# 07_-PowerSupply.net
KiCad netlist of a schematic drawn in Altium Designer
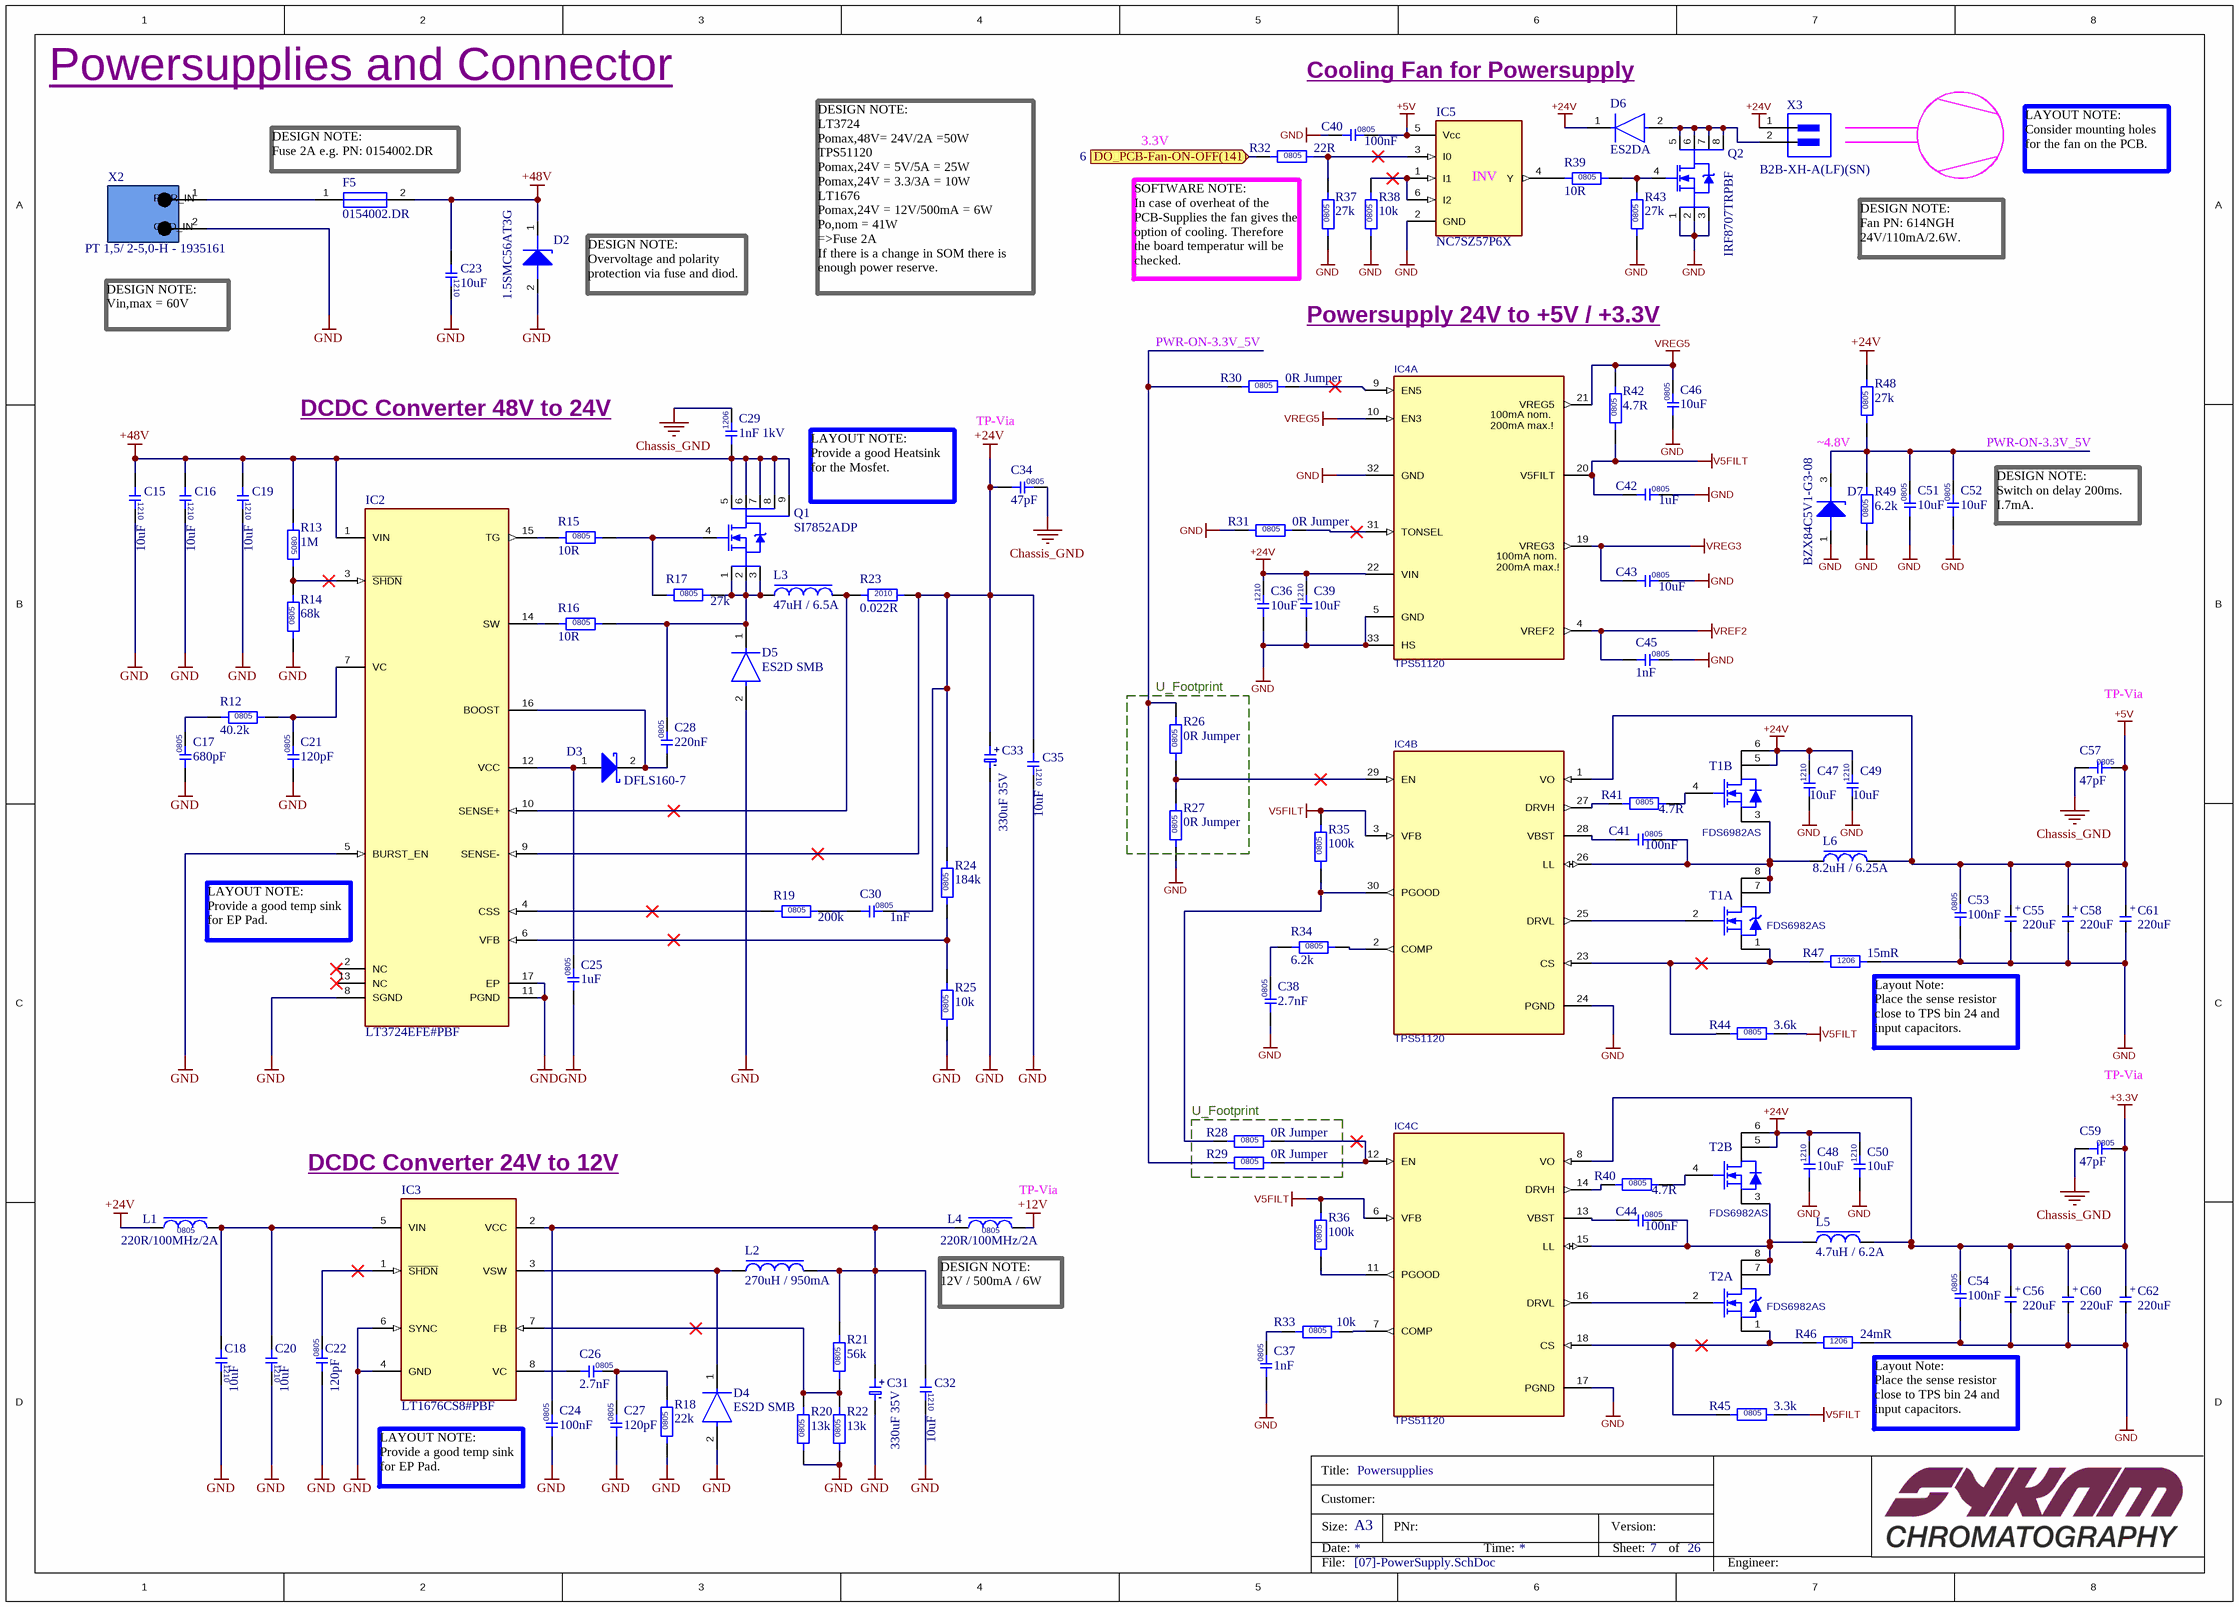
[diagram p0: [07]-PowerSupply.SchDoc]

(export (version "E")
  (design (tool "Eeschema 10.0.6"))
  (components
    (comp (ref "C15")
      (value "10uF")
      (footprint "C1210")
      (description "CAP CER 10UF 50V X7R 1210")
      (fields
        (field (name "MANUFACTURER") "KEMET")
        (field (name "MANUFACTURER PART NUMBER") "C1210C106K5RACTU")
      )
      (libsource (lib "ToradexMainBoard-V0I1") (part "C_10uF_C1210C106K5RACTU"))
    )
    (comp (ref "C16")
      (value "10uF")
      (footprint "C1210")
      (description "CAP CER 10UF 50V X7R 1210")
      (fields
        (field (name "MANUFACTURER") "KEMET")
        (field (name "MANUFACTURER PART NUMBER") "C1210C106K5RACTU")
      )
      (libsource (lib "ToradexMainBoard-V0I1") (part "C_10uF_C1210C106K5RACTU"))
    )
    (comp (ref "C17")
      (value "680pF")
      (footprint "C0805")
      (description "Cap Ceramic 680pF 50V X7R 10% SMD 0805 125C T/R")
      (fields
        (field (name "MANUFACTURER") "KEMET")
        (field (name "MANUFACTURER PART NUMBER") "C0805C681K5RACTU")
      )
      (libsource (lib "ToradexMainBoard-V0I1") (part "C_680pF_C0805C681K5RACTU"))
    )
    (comp (ref "C18")
      (value "10uF")
      (footprint "C1210")
      (description "CAP CER 10UF 50V X7R 1210")
      (fields
        (field (name "MANUFACTURER") "KEMET")
        (field (name "MANUFACTURER PART NUMBER") "C1210C106K5RACTU")
      )
      (libsource (lib "ToradexMainBoard-V0I1") (part "C_10uF_C1210C106K5RACTU"))
    )
    (comp (ref "C19")
      (value "10uF")
      (footprint "C1210")
      (description "CAP CER 10UF 50V X7R 1210")
      (fields
        (field (name "MANUFACTURER") "KEMET")
        (field (name "MANUFACTURER PART NUMBER") "C1210C106K5RACTU")
      )
      (libsource (lib "ToradexMainBoard-V0I1") (part "C_10uF_C1210C106K5RACTU"))
    )
    (comp (ref "C20")
      (value "10uF")
      (footprint "C1210")
      (description "CAP CER 10UF 50V X7R 1210")
      (fields
        (field (name "MANUFACTURER") "KEMET")
        (field (name "MANUFACTURER PART NUMBER") "C1210C106K5RACTU")
      )
      (libsource (lib "ToradexMainBoard-V0I1") (part "C_10uF_C1210C106K5RACTU"))
    )
    (comp (ref "C21")
      (value "120pF")
      (footprint "C0805")
      (description "Cap Ceramic 120pF 50V X7R 10% SMD 0805 125C T/R")
      (fields
        (field (name "MANUFACTURER") "Kyocera AVX")
        (field (name "MANUFACTURER PART NUMBER") "08055C121KAT2A")
      )
      (libsource (lib "ToradexMainBoard-V0I1") (part "C_120pF_08055C121KAT2A"))
    )
    (comp (ref "C22")
      (value "120pF")
      (footprint "C0805")
      (description "Cap Ceramic 120pF 50V X7R 10% SMD 0805 125C T/R")
      (fields
        (field (name "MANUFACTURER") "Kyocera AVX")
        (field (name "MANUFACTURER PART NUMBER") "08055C121KAT2A")
      )
      (libsource (lib "ToradexMainBoard-V0I1") (part "C_120pF_08055C121KAT2A"))
    )
    (comp (ref "C23")
      (value "10uF")
      (footprint "C1210")
      (description "CAP CER 10UF 50V X7R 1210")
      (fields
        (field (name "MANUFACTURER") "KEMET")
        (field (name "MANUFACTURER PART NUMBER") "C1210C106K5RACTU")
      )
      (libsource (lib "ToradexMainBoard-V0I1") (part "C_10uF_C1210C106K5RACTU"))
    )
    (comp (ref "C24")
      (value "100nF")
      (footprint "C0805")
      (description "CAP CER 0.1UF 50V X7R 0805")
      (fields
        (field (name "MANUFACTURER PART NUMBER") "CC0805KRX7R9BB104")
        (field (name "TOLERANCE") "10%")
        (field (name "PCBCHECKED") "initials after Checked")
        (field (name "SCHCHECKED") "Initials after checked")
      )
      (libsource (lib "ToradexMainBoard-V0I1") (part "C_100nF_CC0805KRX7R9BB104"))
    )
    (comp (ref "C25")
      (value "1uF")
      (footprint "C0805")
      (description "Cap Ceramic 1uF 50V X7R 10% SMD 0805 125C Blister T/R")
      (fields
        (field (name "MANUFACTURER PART NUMBER") "CC0805KKX7R9BB105")
        (field (name "TOLERANCE") "10%")
        (field (name "PCBCHECKED") "initials after Checked")
        (field (name "SCHCHECKED") "Initials after checked")
      )
      (libsource (lib "ToradexMainBoard-V0I1") (part "C_1uF_CC0805KKX7R9BB105"))
    )
    (comp (ref "C26")
      (value "2.7nF")
      (footprint "C0805")
      (fields
        (field (name "MANUFACTURER") "KEMET")
        (field (name "MANUFACTURER PART NUMBER") "C0805C272K5RACTU")
        (field (name "TOLERANCE") "10%")
      )
      (libsource (lib "ToradexMainBoard-V0I1") (part "C_2.7nF_C0805C272K5RACTU"))
    )
    (comp (ref "C27")
      (value "120pF")
      (footprint "C0805")
      (description "Cap Ceramic 120pF 50V X7R 10% SMD 0805 125C T/R")
      (fields
        (field (name "MANUFACTURER") "Kyocera AVX")
        (field (name "MANUFACTURER PART NUMBER") "08055C121KAT2A")
      )
      (libsource (lib "ToradexMainBoard-V0I1") (part "C_120pF_08055C121KAT2A"))
    )
    (comp (ref "C28")
      (value "220nF")
      (footprint "C0805")
      (description "CAP CER 0.22UF 50V X7R 0805")
      (fields
        (field (name "MANUFACTURER") "KEMET")
        (field (name "MANUFACTURER PART NUMBER") "C0805C224K5RACTU")
      )
      (libsource (lib "ToradexMainBoard-V0I1") (part "C_220nF_C0805C224K5RACTU"))
    )
    (comp (ref "C29")
      (value "1nF 1kV")
      (footprint "C1206")
      (description "CAP CER 1000PF 1KV X7S 1206")
      (fields
        (field (name "MANUFACTURER") "TDK")
        (field (name "MANUFACTURER PART NUMBER") "CGA5F1X7S3A102M085AE")
      )
      (libsource (lib "Sykam-LagerBauteile1-B") (part "C_1nF-1kV-CGA5F1X7S3A102M085AE"))
    )
    (comp (ref "C30")
      (value "1nF")
      (footprint "C0805")
      (description "Multilayer Ceramic Capacitors MLCC - SMD/SMT 50volts 1000pF X7R 10%")
      (fields
        (field (name "MANUFACTURER") "KEMET")
        (field (name "MANUFACTURER PART NUMBER") "C0805C102K5RAC7411")
      )
      (libsource (lib "ToradexMainBoard-V0I1") (part "C_1nF_C0805C102K5RAC7411"))
    )
    (comp (ref "C31")
      (value "330uF 35V")
      (footprint "C_EEEFP1V331AP")
      (description "GLOVE, POLYAMIDE, L/FREE, PU, SIZE 6 - More Details")
      (fields
        (field (name "MANUFACTURER") "Panasonic")
        (field (name "MANUFACTURER PART NUMBER") "EEEFP1V331AP")
      )
      (libsource (lib "ToradexMainBoard-V0I1") (part "C_330uF_35V_EEEFP1V331AP"))
    )
    (comp (ref "C32")
      (value "10uF")
      (footprint "C1210")
      (description "CAP CER 10UF 50V X7R 1210")
      (fields
        (field (name "MANUFACTURER") "KEMET")
        (field (name "MANUFACTURER PART NUMBER") "C1210C106K5RACTU")
      )
      (libsource (lib "ToradexMainBoard-V0I1") (part "C_10uF_C1210C106K5RACTU"))
    )
    (comp (ref "C33")
      (value "330uF 35V")
      (footprint "C_EEEFP1V331AP")
      (description "GLOVE, POLYAMIDE, L/FREE, PU, SIZE 6 - More Details")
      (fields
        (field (name "MANUFACTURER") "Panasonic")
        (field (name "MANUFACTURER PART NUMBER") "EEEFP1V331AP")
      )
      (libsource (lib "ToradexMainBoard-V0I1") (part "C_330uF_35V_EEEFP1V331AP"))
    )
    (comp (ref "C34")
      (value "47pF")
      (footprint "C0805")
      (description "Capacitor: ceramic; MLCC; 47pF; 100V; C0G; ±5%; SMD; 0805")
      (fields (field (name "MANUFACTURER PART NUMBER") "C0805C470J1GACTU") (field (name "TOLERANCE") "5%"))
      (libsource (lib "ToradexMainBoard-V0I1") (part "C_47pF_C0805C470J1GACTU"))
    )
    (comp (ref "C35")
      (value "10uF")
      (footprint "C1210")
      (description "CAP CER 10UF 50V X7R 1210")
      (fields
        (field (name "MANUFACTURER") "KEMET")
        (field (name "MANUFACTURER PART NUMBER") "C1210C106K5RACTU")
      )
      (libsource (lib "ToradexMainBoard-V0I1") (part "C_10uF_C1210C106K5RACTU"))
    )
    (comp (ref "C36")
      (value "10uF")
      (footprint "C1210")
      (description "CAP CER 10UF 50V X7R 1210")
      (fields
        (field (name "MANUFACTURER") "KEMET")
        (field (name "MANUFACTURER PART NUMBER") "C1210C106K5RACTU")
      )
      (libsource (lib "Sykam-LagerBauteile1") (part "C_10uF_C1210C106K5RACTU"))
    )
    (comp (ref "C37")
      (value "1nF")
      (footprint "C0805")
      (description "Multilayer Ceramic Capacitors MLCC - SMD/SMT 50volts 1000pF X7R 10%")
      (fields
        (field (name "MANUFACTURER") "KEMET")
        (field (name "MANUFACTURER PART NUMBER") "C0805C102K5RAC7411")
      )
      (libsource (lib "Sykam-LagerBauteile1") (part "C_1nF_C0805C102K5RAC7411"))
    )
    (comp (ref "C38")
      (value "2.7nF")
      (footprint "C0805")
      (fields
        (field (name "MANUFACTURER") "KEMET")
        (field (name "MANUFACTURER PART NUMBER") "C0805C272K5RACTU")
        (field (name "TOLERANCE") "10%")
      )
      (libsource (lib "Sykam-LagerBauteile1") (part "C_2.7nF_C0805C272K5RACTU"))
    )
    (comp (ref "C39")
      (value "10uF")
      (footprint "C1210")
      (description "CAP CER 10UF 50V X7R 1210")
      (fields
        (field (name "MANUFACTURER") "KEMET")
        (field (name "MANUFACTURER PART NUMBER") "C1210C106K5RACTU")
      )
      (libsource (lib "Sykam-LagerBauteile1") (part "C_10uF_C1210C106K5RACTU"))
    )
    (comp (ref "C40")
      (value "100nF")
      (footprint "C0805")
      (description "CAP CER 0.1UF 50V X7R 0805")
      (fields
        (field (name "MANUFACTURER PART NUMBER") "CC0805KRX7R9BB104")
        (field (name "TOLERANCE") "10%")
        (field (name "PCBCHECKED") "initials after Checked")
        (field (name "SCHCHECKED") "Initials after checked")
      )
      (libsource (lib "Sykam-LagerBauteile1") (part "C_100nF_CC0805KRX7R9BB104"))
    )
    (comp (ref "C41")
      (value "100nF")
      (footprint "C0805")
      (description "CAP CER 0.1UF 50V X7R 0805")
      (fields
        (field (name "MANUFACTURER PART NUMBER") "CC0805KRX7R9BB104")
        (field (name "TOLERANCE") "10%")
        (field (name "PCBCHECKED") "initials after Checked")
        (field (name "SCHCHECKED") "Initials after checked")
      )
      (libsource (lib "Sykam-LagerBauteile1") (part "C_100nF_CC0805KRX7R9BB104"))
    )
    (comp (ref "C42")
      (value "1uF")
      (footprint "C0805")
      (description "Cap Ceramic 1uF 50V X7R 10% SMD 0805 125C Blister T/R")
      (fields
        (field (name "MANUFACTURER PART NUMBER") "CC0805KKX7R9BB105")
        (field (name "TOLERANCE") "10%")
        (field (name "PCBCHECKED") "initials after Checked")
        (field (name "SCHCHECKED") "Initials after checked")
      )
      (libsource (lib "Sykam-LagerBauteile1") (part "C_1uF_CC0805KKX7R9BB105"))
    )
    (comp (ref "C43")
      (value "10uF")
      (footprint "C0805")
      (description "0805 10 uF 50 V ±20% Tolerance X5R Multilayer Ceramic Capacitor")
      (fields
        (field (name "MANUFACTURER") "Murata")
        (field (name "MANUFACTURER PART NUMBER") "GRM21BR6YA106ME43L")
      )
      (libsource (lib "Sykam-LagerBauteile1") (part "C_10uF_GRM21BR6YA106ME43L"))
    )
    (comp (ref "C44")
      (value "100nF")
      (footprint "C0805")
      (description "CAP CER 0.1UF 50V X7R 0805")
      (fields
        (field (name "MANUFACTURER PART NUMBER") "CC0805KRX7R9BB104")
        (field (name "TOLERANCE") "10%")
        (field (name "PCBCHECKED") "initials after Checked")
        (field (name "SCHCHECKED") "Initials after checked")
      )
      (libsource (lib "Sykam-LagerBauteile1") (part "C_100nF_CC0805KRX7R9BB104"))
    )
    (comp (ref "C45")
      (value "1nF")
      (footprint "C0805")
      (description "Multilayer Ceramic Capacitors MLCC - SMD/SMT 50volts 1000pF X7R 10%")
      (fields
        (field (name "MANUFACTURER") "KEMET")
        (field (name "MANUFACTURER PART NUMBER") "C0805C102K5RAC7411")
      )
      (libsource (lib "Sykam-LagerBauteile1") (part "C_1nF_C0805C102K5RAC7411"))
    )
    (comp (ref "C46")
      (value "10uF")
      (footprint "C0805")
      (description "0805 10 uF 50 V ±20% Tolerance X5R Multilayer Ceramic Capacitor")
      (fields
        (field (name "MANUFACTURER") "Murata")
        (field (name "MANUFACTURER PART NUMBER") "GRM21BR6YA106ME43L")
      )
      (libsource (lib "Sykam-LagerBauteile1") (part "C_10uF_GRM21BR6YA106ME43L"))
    )
    (comp (ref "C47")
      (value "10uF")
      (footprint "C1210")
      (description "CAP CER 10UF 50V X7R 1210")
      (fields
        (field (name "MANUFACTURER") "KEMET")
        (field (name "MANUFACTURER PART NUMBER") "C1210C106K5RACTU")
      )
      (libsource (lib "Sykam-LagerBauteile1") (part "C_10uF_C1210C106K5RACTU"))
    )
    (comp (ref "C48")
      (value "10uF")
      (footprint "C1210")
      (description "CAP CER 10UF 50V X7R 1210")
      (fields
        (field (name "MANUFACTURER") "KEMET")
        (field (name "MANUFACTURER PART NUMBER") "C1210C106K5RACTU")
      )
      (libsource (lib "Sykam-LagerBauteile1") (part "C_10uF_C1210C106K5RACTU"))
    )
    (comp (ref "C49")
      (value "10uF")
      (footprint "C1210")
      (description "CAP CER 10UF 50V X7R 1210")
      (fields
        (field (name "MANUFACTURER") "KEMET")
        (field (name "MANUFACTURER PART NUMBER") "C1210C106K5RACTU")
      )
      (libsource (lib "Sykam-LagerBauteile1") (part "C_10uF_C1210C106K5RACTU"))
    )
    (comp (ref "C50")
      (value "10uF")
      (footprint "C1210")
      (description "CAP CER 10UF 50V X7R 1210")
      (fields
        (field (name "MANUFACTURER") "KEMET")
        (field (name "MANUFACTURER PART NUMBER") "C1210C106K5RACTU")
      )
      (libsource (lib "Sykam-LagerBauteile1") (part "C_10uF_C1210C106K5RACTU"))
    )
    (comp (ref "C51")
      (value "10uF")
      (footprint "C0805")
      (description "0805 10 uF 50 V ±20% Tolerance X5R Multilayer Ceramic Capacitor")
      (fields
        (field (name "MANUFACTURER") "Murata")
        (field (name "MANUFACTURER PART NUMBER") "GRM21BR6YA106ME43L")
      )
      (libsource (lib "ToradexMainBoard-V0I1") (part "C_10uF_GRM21BR6YA106ME43L"))
    )
    (comp (ref "C52")
      (value "10uF")
      (footprint "C0805")
      (description "0805 10 uF 50 V ±20% Tolerance X5R Multilayer Ceramic Capacitor")
      (fields
        (field (name "MANUFACTURER") "Murata")
        (field (name "MANUFACTURER PART NUMBER") "GRM21BR6YA106ME43L")
      )
      (libsource (lib "ToradexMainBoard-V0I1") (part "C_10uF_GRM21BR6YA106ME43L"))
    )
    (comp (ref "C53")
      (value "100nF")
      (footprint "C0805")
      (description "CAP CER 0.1UF 50V X7R 0805")
      (fields
        (field (name "MANUFACTURER PART NUMBER") "CC0805KRX7R9BB104")
        (field (name "TOLERANCE") "10%")
        (field (name "PCBCHECKED") "initials after Checked")
        (field (name "SCHCHECKED") "Initials after checked")
      )
      (libsource (lib "Sykam-LagerBauteile1") (part "C_100nF_CC0805KRX7R9BB104"))
    )
    (comp (ref "C54")
      (value "100nF")
      (footprint "C0805")
      (description "CAP CER 0.1UF 50V X7R 0805")
      (fields
        (field (name "MANUFACTURER PART NUMBER") "CC0805KRX7R9BB104")
        (field (name "TOLERANCE") "10%")
        (field (name "PCBCHECKED") "initials after Checked")
        (field (name "SCHCHECKED") "Initials after checked")
      )
      (libsource (lib "Sykam-LagerBauteile1") (part "C_100nF_CC0805KRX7R9BB104"))
    )
    (comp (ref "C55")
      (value "220uF")
      (footprint "C_220uF_TAN_TPSD227M010R0100")
      (description "CAPACITOR, TANTALUM")
      (fields
        (field (name "MANUFACTURER") "Kyocera AVX")
        (field (name "MANUFACTURER PART NUMBER") "TPSD227M010R0100")
      )
      (libsource (lib "Sykam-LagerBauteile1") (part "C_220uF_TAN_TPSD227M010R0100"))
    )
    (comp (ref "C56")
      (value "220uF")
      (footprint "C_220uF_TAN_TPSD227M010R0100")
      (description "CAPACITOR, TANTALUM")
      (fields
        (field (name "MANUFACTURER") "Kyocera AVX")
        (field (name "MANUFACTURER PART NUMBER") "TPSD227M010R0100")
      )
      (libsource (lib "Sykam-LagerBauteile1") (part "C_220uF_TAN_TPSD227M010R0100"))
    )
    (comp (ref "C57")
      (value "47pF")
      (footprint "C0805")
      (description "Capacitor: ceramic; MLCC; 47pF; 100V; C0G; ±5%; SMD; 0805")
      (fields (field (name "MANUFACTURER PART NUMBER") "C0805C470J1GACTU") (field (name "TOLERANCE") "5%"))
      (libsource (lib "ToradexMainBoard-V0I1") (part "C_47pF_C0805C470J1GACTU"))
    )
    (comp (ref "C58")
      (value "220uF")
      (footprint "C_220uF_TAN_TPSD227M010R0100")
      (description "CAPACITOR, TANTALUM")
      (fields
        (field (name "MANUFACTURER") "Kyocera AVX")
        (field (name "MANUFACTURER PART NUMBER") "TPSD227M010R0100")
      )
      (libsource (lib "Sykam-LagerBauteile1") (part "C_220uF_TAN_TPSD227M010R0100"))
    )
    (comp (ref "C59")
      (value "47pF")
      (footprint "C0805")
      (description "Capacitor: ceramic; MLCC; 47pF; 100V; C0G; ±5%; SMD; 0805")
      (fields (field (name "MANUFACTURER PART NUMBER") "C0805C470J1GACTU") (field (name "TOLERANCE") "5%"))
      (libsource (lib "ToradexMainBoard-V0I1") (part "C_47pF_C0805C470J1GACTU"))
    )
    (comp (ref "C60")
      (value "220uF")
      (footprint "C_220uF_TAN_TPSD227M010R0100")
      (description "CAPACITOR, TANTALUM")
      (fields
        (field (name "MANUFACTURER") "Kyocera AVX")
        (field (name "MANUFACTURER PART NUMBER") "TPSD227M010R0100")
      )
      (libsource (lib "Sykam-LagerBauteile1") (part "C_220uF_TAN_TPSD227M010R0100"))
    )
    (comp (ref "C61")
      (value "220uF")
      (footprint "C_220uF_TAN_TPSD227M010R0100")
      (description "CAPACITOR, TANTALUM")
      (fields
        (field (name "MANUFACTURER") "Kyocera AVX")
        (field (name "MANUFACTURER PART NUMBER") "TPSD227M010R0100")
      )
      (libsource (lib "Sykam-LagerBauteile1") (part "C_220uF_TAN_TPSD227M010R0100"))
    )
    (comp (ref "C62")
      (value "220uF")
      (footprint "C_220uF_TAN_TPSD227M010R0100")
      (description "CAPACITOR, TANTALUM")
      (fields
        (field (name "MANUFACTURER") "Kyocera AVX")
        (field (name "MANUFACTURER PART NUMBER") "TPSD227M010R0100")
      )
      (libsource (lib "Sykam-LagerBauteile1") (part "C_220uF_TAN_TPSD227M010R0100"))
    )
    (comp (ref "D2")
      (value "1.5SMC56AT3G")
      (footprint "D-TVS_SMC_UNI")
      (description "TVS DIODE 47.8V 77V SMC")
      (fields (field (name "MANUFACTURER") "ON Semiconductor"))
      (libsource (lib "ToradexMainBoard-V0I1") (part "D_TVS_1.5SMC56AT3G"))
    )
    (comp (ref "D3")
      (value "DFLS160-7")
      (footprint "D_POWERDI123")
      (description "DIODES INC. - DFLS160-7 - Schottky Rectifier, 60 V, 1 A, Single, PowerDI 123, 2 Pins, 500 mV")
      (fields (field (name "MANUFACTURER") "Diodes"))
      (libsource (lib "ToradexMainBoard-V0I1") (part "D_DFLS160-7"))
    )
    (comp (ref "D4")
      (value "ES2D SMB")
      (footprint "FB-SMB")
      (description "ON SEMICONDUCTOR - ES2D - Fast / Ultrafast Diode, 200 V, 2 A, Single, 900 mV, 20 ns, 50 A")
      (fields
        (field (name "MANUFACTURER") "ON Semiconductor / Fairchild")
        (field (name "MANUFACTURER PART NUMBER") "ES2D")
      )
      (libsource (lib "ToradexMainBoard-V0I1") (part "D_ES2D-SMB"))
    )
    (comp (ref "D5")
      (value "ES2D SMB")
      (footprint "FB-SMB")
      (description "ON SEMICONDUCTOR - ES2D - Fast / Ultrafast Diode, 200 V, 2 A, Single, 900 mV, 20 ns, 50 A")
      (fields
        (field (name "MANUFACTURER") "ON Semiconductor / Fairchild")
        (field (name "MANUFACTURER PART NUMBER") "ES2D")
      )
      (libsource (lib "ToradexMainBoard-V0I1") (part "D_ES2D-SMB"))
    )
    (comp (ref "D6")
      (value "ES2DA")
      (footprint "FP-SMA-MFG")
      (description "DIODE GEN PURP 200V 2A SMA")
      (fields (field (name "MANUFACTURER") "Diodes") (field (name "MANUFACTURER PART NUMBER") "ES2DA-13-F"))
      (libsource (lib "Sykam-LagerBauteile1-B") (part "D_ES2DA-13-F"))
    )
    (comp (ref "D7")
      (value "BZX84C5V1-G3-08")
      (footprint "BZX84C5.1V-SOT-23-3")
      (description "Zener Diodes 5.1 Volt 0.35W 5%")
      (fields (field (name "MANUFACTURER") "Vishay") (field (name "TOLERANCE") "5%"))
      (libsource (lib "ToradexMainBoard-V0I1") (part "D_BZX84C5V1-G3-08"))
    )
    (comp (ref "F5")
      (value "0154002.DR")
      (footprint "F_FUSE-154002")
      (description "LITTELFUSE   0154002.DR.   FUSE BLOCK W/ 2A FUSE, FAST ACTING")
      (fields (field (name "MANUFACTURER") "Littelfuse"))
      (libsource (lib "ToradexMainBoard-V0I1") (part "F_Fuse-0154002.DR"))
    )
    (comp (ref "IC2")
      (value "LT3724EFE#PBF")
      (footprint "LT3724_LT-FE-16-EPV-BC_L")
      (description "LINEAR TECHNOLOGY 	   	LT3724EFE#PBF 	   	IC, SWITCHING REGULATOR CTRL, 16-TSSOP")
      (fields (field (name "MANUFACTURER") "Analog Devices / Linear Technology"))
      (libsource (lib "ToradexMainBoard-V0I1") (part "IC_LT3724EFE#PBF"))
    )
    (comp (ref "IC3")
      (value "LT1676CS8#PBF")
      (footprint "LT1676-SOIC8")
      (description "IC REG BUCK ADJ 0.55A 8SOIC")
      (fields (field (name "MANUFACTURER") "Analog Devices / Linear Technology"))
      (libsource (lib "ToradexMainBoard-V0I1") (part "IC_LT1676CS8#PBF"))
    )
    (comp (ref "IC4")
      (value "TPS51120")
      (footprint "QFN50P500X500X100-33N")
      (description "IC REG CTRLR BUCK 32QFN")
      (fields
        (field (name "MANUFACTURER PART NO.") "TPS51120")
        (field (name "MANUFACTURER") "Texas Instruments")
        (field (name "MANUFACTURER PART NUMBER") "TPS51120RHBT")
      )
      (libsource (lib "Evaluation Board") (part "IC-TI-TPS51120"))
    )
    (comp (ref "IC5")
      (value "NC7SZ57P6X")
      (footprint "NC7SZ57P6X")
      (fields
        (field (name "MANUFACTURER") "ON Semiconductor / Fairchild")
        (field (name "PCBCHECKED") "initials after Checked")
        (field (name "SCHCHECKED") "Initials after checked")
      )
      (libsource (lib "Sykam-LagerBauteile1") (part "IC_NC7SZ57P6X"))
    )
    (comp (ref "L1")
      (value "220R/100MHz/2A")
      (footprint "L0805")
      (description "Ferrite Beads Multi-Layer 220Ohm 25% 100MHz 2A 45mOhm DCR 0805 Paper T/R")
      (fields
        (field (name "MANUFACTURER PART NUMBER") "BLM21PG221SN1D")
        (field (name "TOLERANCE") "25%")
        (field (name "PCBCHECKED") "initials after Checked")
        (field (name "SCHCHECKED") "Initials after checked")
      )
      (libsource (lib "ToradexMainBoard-V0I1") (part "L_BLM21PG221SN1D"))
    )
    (comp (ref "L2")
      (value "270uH / 950mA")
      (footprint "L_SRR1208_271KL")
      (description "Inductor Power Shielded Wirewound 270uH 10% 1KHz 13Q-Factor Ferrite 950mA 400mOhm DCR T/R")
      (fields
        (field (name "MANUFACTURER") "Bourns")
        (field (name "MANUFACTURER PART NUMBER") "SRR1208-271KL")
      )
      (libsource (lib "ToradexMainBoard-V0I1") (part "L_270uH_SRR1208-271KL"))
    )
    (comp (ref "L3")
      (value "47uH / 6.5A")
      (footprint "L_SRP1265A")
      (description "FIXED IND 47UH 6.5A 90 MOHM SMD")
      (fields
        (field (name "MANUFACTURER") "Bourns")
        (field (name "MANUFACTURER PART NUMBER") "SRP1265A-470M")
      )
      (libsource (lib "ToradexMainBoard-V0I1") (part "L_47uH_SRP1265A-470M"))
    )
    (comp (ref "L4")
      (value "220R/100MHz/2A")
      (footprint "L0805")
      (description "Ferrite Beads Multi-Layer 220Ohm 25% 100MHz 2A 45mOhm DCR 0805 Paper T/R")
      (fields
        (field (name "MANUFACTURER PART NUMBER") "BLM21PG221SN1D")
        (field (name "TOLERANCE") "25%")
        (field (name "PCBCHECKED") "initials after Checked")
        (field (name "SCHCHECKED") "Initials after checked")
      )
      (libsource (lib "ToradexMainBoard-V0I1") (part "L_BLM21PG221SN1D"))
    )
    (comp (ref "L5")
      (value "4.7uH / 6.2A")
      (footprint "7447797470-WE-PDF-1045")
      (fields
        (field (name "MANUFACTURER") "Wurth Electronics")
        (field (name "MANUFACTURER PART NUMBER") "7447797470")
        (field (name "TOLERANCE") "20%")
      )
      (libsource (lib "Sykam-LagerBauteile1-B") (part "L_7447797470"))
    )
    (comp (ref "L6")
      (value "8.2uH / 6.25A")
      (footprint "744771008-WE-PD-L")
      (description "Inductor, SMD 8.2 uH 6.25 A ±20%, 744771008, Würth Elektronik")
      (fields
        (field (name "MANUFACTURER") "Wurth Electronics")
        (field (name "MANUFACTURER PART NUMBER") "744771008")
      )
      (libsource (lib "Sykam-LagerBauteile1-B") (part "L_744771008"))
    )
    (comp (ref "Q1")
      (value "SI7852ADP")
      (footprint "SI7852ADP_NMOS-PowerPAK-SO-8")
      (description "MOSFET N-CH 80V 30A PPAK SO-8")
      (fields
        (field (name "MANUFACTURER") "Vishay Siliconix")
        (field (name "MANUFACTURER PART NUMBER") "SI7852ADP-T1-GE3")
      )
      (libsource (lib "ToradexMainBoard-V0I1") (part "Q_NMOS_SI7852ADP-T1-GE3"))
    )
    (comp (ref "Q2")
      (value "IRF8707TRPBF")
      (footprint "IRF8707_SOIC8")
      (description "MOSFET N-CH 30V 11A 8-SOIC")
      (fields (field (name "MANUFACTURER") "International Rectifier"))
      (libsource (lib "Sykam-LagerBauteile1-B") (part "Q_IRF8707TRPBF"))
    )
    (comp (ref "R12")
      (value "40.2k")
      (footprint "R0805")
      (description "Resistor,Ruthenium Oxide,40.2KOhms,100WV,1+/-% Tol,-100,100ppm-TC,0805-Case ;RoHS Compliant: Yes")
      (fields
        (field (name "MANUFACTURER") "Bourns")
        (field (name "MANUFACTURER PART NUMBER") "CR0805-FX-4022ELF")
      )
      (libsource (lib "ToradexMainBoard-V0I1") (part "R_40.2k_CR0805-FX-4022ELF"))
    )
    (comp (ref "R13")
      (value "1M")
      (footprint "R0805")
      (description "Res Thick Film 0805 1M Ohm 1% 0.125W(1/8W) ±100ppm/C Epoxy SMD T/R")
      (fields
        (field (name "MANUFACTURER") "Yageo")
        (field (name "MANUFACTURER PART NUMBER") "RC0805FR-071ML")
      )
      (libsource (lib "ToradexMainBoard-V0I1") (part "R_1M_RC0805FR-071ML"))
    )
    (comp (ref "R14")
      (value "68k")
      (footprint "R0805")
      (fields
        (field (name "MANUFACTURER") "Vishay")
        (field (name "MANUFACTURER PART NUMBER") "CRCW080568K0FKEA")
        (field (name "TOLERANCE") "1%")
      )
      (libsource (lib "ToradexMainBoard-V0I1") (part "R_68k_CRCW080568K0FKEA"))
    )
    (comp (ref "R15")
      (value "10R")
      (footprint "R0805")
      (description "YAGEO (PHYCOMP) - RC0805FR-0710RL - RES, THICK FILM, 10R, 1%, 0.125W, 0805")
      (fields
        (field (name "MANUFACTURER PART NUMBER") "RC0805FR-0710RL")
        (field (name "TOLERANCE") "1%")
        (field (name "PCBCHECKED") "initials after Checked")
        (field (name "SCHCHECKED") "Initials after checked")
      )
      (libsource (lib "ToradexMainBoard-V0I1") (part "R_10R_RC0805FR-0710RL"))
    )
    (comp (ref "R16")
      (value "10R")
      (footprint "R0805")
      (description "YAGEO (PHYCOMP) - RC0805FR-0710RL - RES, THICK FILM, 10R, 1%, 0.125W, 0805")
      (fields
        (field (name "MANUFACTURER PART NUMBER") "RC0805FR-0710RL")
        (field (name "TOLERANCE") "1%")
        (field (name "PCBCHECKED") "initials after Checked")
        (field (name "SCHCHECKED") "Initials after checked")
      )
      (libsource (lib "ToradexMainBoard-V0I1") (part "R_10R_RC0805FR-0710RL"))
    )
    (comp (ref "R17")
      (value "27k")
      (footprint "R0805")
      (description "Surface Mount Thick Film Resistor, RC Series, 27 kohm, 125 mW, - 1%, 150 V, 0805 [2012 Metric]")
      (fields
        (field (name "MANUFACTURER") "Yageo")
        (field (name "MANUFACTURER PART NUMBER") "RC0805FR-0727KL")
      )
      (libsource (lib "ToradexMainBoard-V0I1") (part "R_27k_RC0805FR-0727KL"))
    )
    (comp (ref "R18")
      (value "22k")
      (footprint "R0805")
      (description "TT ELECTRONICS / WELWYN - WCR0805-22KFI - RES, 22K, 1%, 0.125W, 0805, THICK FILM")
      (fields
        (field (name "MANUFACTURER") "TT Welwyn")
        (field (name "MANUFACTURER PART NUMBER") "WCR0805-22KFI")
      )
      (libsource (lib "ToradexMainBoard-V0I1") (part "R_22k_WCR0805-22KFI"))
    )
    (comp (ref "R19")
      (value "200k")
      (footprint "R0805")
      (description "YAGEO - RC0805FR-07200KL - RES, THICK FILM, 200K, 1%, 0.125W, 0805, REEL")
      (fields
        (field (name "MANUFACTURER") "Yageo")
        (field (name "MANUFACTURER PART NUMBER") "RC0805FR-07200KL")
      )
      (libsource (lib "ToradexMainBoard-V0I1") (part "R_200k_RC0805FR-07200KL"))
    )
    (comp (ref "R20")
      (value "13k")
      (footprint "R0805")
      (description "Res Thick Film 2.0 x 1.2 mm 13K Ohm 1% 0.125W(1/8W) 100ppm/ C Molded SMD Paper T/R")
      (fields
        (field (name "MANUFACTURER") "Yageo")
        (field (name "MANUFACTURER PART NUMBER") "RC0805FR-0713KL")
      )
      (libsource (lib "ToradexMainBoard-V0I1") (part "R_13k_RC0805FR-0713KL"))
    )
    (comp (ref "R21")
      (value "56k")
      (footprint "R0805")
      (description "SMD Resistor, Thick film 56 kOhm,  ±  1 %, 0805, CRCW080556K0FKEA, Vishay")
      (fields
        (field (name "MANUFACTURER") "Vishay")
        (field (name "MANUFACTURER PART NUMBER") "CRCW080556K0FKEA")
      )
      (libsource (lib "ToradexMainBoard-V0I1") (part "R_56k_CRCW080556K0FKEA"))
    )
    (comp (ref "R22")
      (value "13k")
      (footprint "R0805")
      (description "Res Thick Film 2.0 x 1.2 mm 13K Ohm 1% 0.125W(1/8W) 100ppm/ C Molded SMD Paper T/R")
      (fields
        (field (name "MANUFACTURER") "Yageo")
        (field (name "MANUFACTURER PART NUMBER") "RC0805FR-0713KL")
      )
      (libsource (lib "ToradexMainBoard-V0I1") (part "R_13k_RC0805FR-0713KL"))
    )
    (comp (ref "R23")
      (value "0.022R")
      (footprint "R2010")
      (description "Res Metal Strip 2010 0.022 Ohm 1% 1/2W 75ppm/C Molded SMD SMD Embossed Plastic T/R")
      (fields
        (field (name "MANUFACTURER") "Vishay Dale")
        (field (name "MANUFACTURER PART NUMBER") "WSL2010R0220FEA")
      )
      (libsource (lib "ToradexMainBoard-V0I1") (part "R_0.022R_WSL2010R0220FEA"))
    )
    (comp (ref "R24")
      (value "184k")
      (footprint "R0805")
      (description "Thin Film Resistors - SMD 25ppm 184Kohms .1%")
      (fields
        (field (name "MANUFACTURER") "Vishay Dale")
        (field (name "MANUFACTURER PART NUMBER") "PTN0805E1843BBT0")
      )
      (libsource (lib "ToradexMainBoard-V0I1") (part "R_184k_PTN0805E1843BBT0"))
    )
    (comp (ref "R25")
      (value "10k")
      (footprint "R0805")
      (description "RES SMD 10K OHM 1% 1/8W 0805")
      (fields
        (field (name "MANUFACTURER PART NUMBER") "RC0805FR-0710KL")
        (field (name "TOLERANCE") "1%")
        (field (name "PCBCHECKED") "initials after Checked")
        (field (name "SCHCHECKED") "Initials after checked")
      )
      (libsource (lib "ToradexMainBoard-V0I1") (part "R_10k_RC0805FR-0710KL"))
    )
    (comp (ref "R26")
      (value "0R Jumper")
      (footprint "R0805")
      (fields
        (field (name "MANUFACTURER PART NUMBER") "RMCF0805ZT0R00")
        (field (name "MANUFACTURER") "Stackpole Electronics")
        (field (name "PCBCHECKED") "initials after Checked")
        (field (name "SCHCHECKED") "Initials after checked")
      )
      (libsource (lib "Sykam-LagerBauteile1") (part "R_0R_RMCF0805ZT0R00"))
    )
    (comp (ref "R27")
      (value "0R Jumper")
      (footprint "R0805")
      (fields
        (field (name "MANUFACTURER PART NUMBER") "RMCF0805ZT0R00")
        (field (name "MANUFACTURER") "Stackpole Electronics")
        (field (name "PCBCHECKED") "initials after Checked")
        (field (name "SCHCHECKED") "Initials after checked")
      )
      (libsource (lib "Sykam-LagerBauteile1") (part "R_0R_RMCF0805ZT0R00"))
    )
    (comp (ref "R28")
      (value "0R Jumper")
      (footprint "R0805")
      (fields
        (field (name "MANUFACTURER PART NUMBER") "RMCF0805ZT0R00")
        (field (name "MANUFACTURER") "Stackpole Electronics")
        (field (name "PCBCHECKED") "initials after Checked")
        (field (name "SCHCHECKED") "Initials after checked")
      )
      (libsource (lib "Sykam-LagerBauteile1") (part "R_0R_RMCF0805ZT0R00"))
    )
    (comp (ref "R29")
      (value "0R Jumper")
      (footprint "R0805")
      (fields
        (field (name "MANUFACTURER PART NUMBER") "RMCF0805ZT0R00")
        (field (name "MANUFACTURER") "Stackpole Electronics")
        (field (name "PCBCHECKED") "initials after Checked")
        (field (name "SCHCHECKED") "Initials after checked")
      )
      (libsource (lib "Sykam-LagerBauteile1") (part "R_0R_RMCF0805ZT0R00"))
    )
    (comp (ref "R30")
      (value "0R Jumper")
      (footprint "R0805")
      (fields
        (field (name "MANUFACTURER PART NUMBER") "RMCF0805ZT0R00")
        (field (name "MANUFACTURER") "Stackpole Electronics")
        (field (name "PCBCHECKED") "initials after Checked")
        (field (name "SCHCHECKED") "Initials after checked")
      )
      (libsource (lib "Sykam-LagerBauteile1") (part "R_0R_RMCF0805ZT0R00"))
    )
    (comp (ref "R31")
      (value "0R Jumper")
      (footprint "R0805")
      (fields
        (field (name "MANUFACTURER PART NUMBER") "RMCF0805ZT0R00")
        (field (name "MANUFACTURER") "Stackpole Electronics")
        (field (name "PCBCHECKED") "initials after Checked")
        (field (name "SCHCHECKED") "Initials after checked")
      )
      (libsource (lib "Sykam-LagerBauteile1") (part "R_0R_RMCF0805ZT0R00"))
    )
    (comp (ref "R32")
      (value "22R")
      (footprint "R0805")
      (description "RES SMD 22 OHM 1% 1/8W 0805")
      (fields
        (field (name "MANUFACTURER PART NUMBER") "RC0805FR-0722RL")
        (field (name "TOLERANCE") "1%")
        (field (name "PCBCHECKED") "initials after Checked")
        (field (name "SCHCHECKED") "Initials after checked")
      )
      (libsource (lib "Sykam-LagerBauteile1-B") (part "R_22R_RC0805FR-0722RL"))
    )
    (comp (ref "R33")
      (value "10k")
      (footprint "R0805")
      (description "RES SMD 10K OHM 1% 1/8W 0805")
      (fields
        (field (name "MANUFACTURER PART NUMBER") "RC0805FR-0710KL")
        (field (name "TOLERANCE") "1%")
        (field (name "PCBCHECKED") "initials after Checked")
        (field (name "SCHCHECKED") "Initials after checked")
      )
      (libsource (lib "Sykam-LagerBauteile1") (part "R_10k_RC0805FR-0710KL"))
    )
    (comp (ref "R34")
      (value "6.2k")
      (footprint "R0805")
      (description "Res Thick Film 0805 6.2K Ohm 1% 0.125W(1/8W) ±100ppm/C Epoxy Pad SMD T/R")
      (fields
        (field (name "MANUFACTURER") "Yageo Phycomp")
        (field (name "MANUFACTURER PART NUMBER") "RC0805FR-076K2L")
      )
      (libsource (lib "Sykam-LagerBauteile1") (part "R_6.2k_RC0805FR-076K2L"))
    )
    (comp (ref "R35")
      (value "100k")
      (footprint "R0805")
      (description "RES SMD 100K OHM 1% 1/8W 0805")
      (fields
        (field (name "MANUFACTURER PART NUMBER") "RC0805FR-07100KL")
        (field (name "TOLERANCE") "1%")
        (field (name "PCBCHECKED") "initials after Checked")
        (field (name "SCHCHECKED") "Initials after checked")
      )
      (libsource (lib "Sykam-LagerBauteile1") (part "R_100k_RC0805FR-07100KL"))
    )
    (comp (ref "R36")
      (value "100k")
      (footprint "R0805")
      (description "RES SMD 100K OHM 1% 1/8W 0805")
      (fields
        (field (name "MANUFACTURER PART NUMBER") "RC0805FR-07100KL")
        (field (name "TOLERANCE") "1%")
        (field (name "PCBCHECKED") "initials after Checked")
        (field (name "SCHCHECKED") "Initials after checked")
      )
      (libsource (lib "Sykam-LagerBauteile1") (part "R_100k_RC0805FR-07100KL"))
    )
    (comp (ref "R37")
      (value "27k")
      (footprint "R0805")
      (description "Surface Mount Thick Film Resistor, RC Series, 27 kohm, 125 mW, - 1%, 150 V, 0805 [2012 Metric]")
      (fields
        (field (name "MANUFACTURER") "Yageo")
        (field (name "MANUFACTURER PART NUMBER") "RC0805FR-0727KL")
      )
      (libsource (lib "Sykam-LagerBauteile1-B") (part "R_27k_RC0805FR-0727KL"))
    )
    (comp (ref "R38")
      (value "10k")
      (footprint "R0805")
      (description "RES SMD 10K OHM 1% 1/8W 0805")
      (fields
        (field (name "MANUFACTURER PART NUMBER") "RC0805FR-0710KL")
        (field (name "TOLERANCE") "1%")
        (field (name "PCBCHECKED") "initials after Checked")
        (field (name "SCHCHECKED") "Initials after checked")
      )
      (libsource (lib "ToradexMainBoard-V0I1") (part "R_10k_RC0805FR-0710KL"))
    )
    (comp (ref "R39")
      (value "10R")
      (footprint "R0805")
      (description "YAGEO (PHYCOMP) - RC0805FR-0710RL - RES, THICK FILM, 10R, 1%, 0.125W, 0805")
      (fields
        (field (name "MANUFACTURER PART NUMBER") "RC0805FR-0710RL")
        (field (name "TOLERANCE") "1%")
        (field (name "PCBCHECKED") "initials after Checked")
        (field (name "SCHCHECKED") "Initials after checked")
      )
      (libsource (lib "Sykam-LagerBauteile1-B") (part "R_10R_RC0805FR-0710RL"))
    )
    (comp (ref "R40")
      (value "4.7R")
      (footprint "R0805")
      (fields
        (field (name "MANUFACTURER") "Yageo")
        (field (name "MANUFACTURER PART NUMBER") "RC0805FR-074R7L")
        (field (name "TOLERANCE") "1%")
      )
      (libsource (lib "Sykam-LagerBauteile1") (part "R_4.7R_RC0805FR-074R7L"))
    )
    (comp (ref "R41")
      (value "4.7R")
      (footprint "R0805")
      (fields
        (field (name "MANUFACTURER") "Yageo")
        (field (name "MANUFACTURER PART NUMBER") "RC0805FR-074R7L")
        (field (name "TOLERANCE") "1%")
      )
      (libsource (lib "Sykam-LagerBauteile1") (part "R_4.7R_RC0805FR-074R7L"))
    )
    (comp (ref "R42")
      (value "4.7R")
      (footprint "R0805")
      (fields
        (field (name "MANUFACTURER") "Yageo")
        (field (name "MANUFACTURER PART NUMBER") "RC0805FR-074R7L")
        (field (name "TOLERANCE") "1%")
      )
      (libsource (lib "Sykam-LagerBauteile1") (part "R_4.7R_RC0805FR-074R7L"))
    )
    (comp (ref "R43")
      (value "27k")
      (footprint "R0805")
      (description "Surface Mount Thick Film Resistor, RC Series, 27 kohm, 125 mW, - 1%, 150 V, 0805 [2012 Metric]")
      (fields
        (field (name "MANUFACTURER") "Yageo")
        (field (name "MANUFACTURER PART NUMBER") "RC0805FR-0727KL")
      )
      (libsource (lib "Sykam-LagerBauteile1-B") (part "R_27k_RC0805FR-0727KL"))
    )
    (comp (ref "R44")
      (value "3.6k")
      (footprint "R0805")
      (description "RES SMD 3.6K OHM 1% 1/8W 0805")
      (fields
        (field (name "MANUFACTURER") "Yageo")
        (field (name "MANUFACTURER PART NUMBER") "RC0805FR-073K6L")
      )
      (libsource (lib "Sykam-LagerBauteile1") (part "R_3.6k_RC0805FR-073K6L"))
    )
    (comp (ref "R45")
      (value "3.3k")
      (footprint "R0805")
      (description "Res Thick Film 0805 3.3K Ohm 1% 0.125W(1/8W) ±100ppm/C Epoxy Pad SMD T/R")
      (fields
        (field (name "MANUFACTURER") "Yageo")
        (field (name "MANUFACTURER PART NUMBER") "RC0805FR-073K3L")
      )
      (libsource (lib "Sykam-LagerBauteile1") (part "R_3.3k_RC0805FR-073K3L"))
    )
    (comp (ref "R46")
      (value "24mR")
      (footprint "R1206")
      (description "Current Sense Resistors - SMD 0.024ohm 1%")
      (fields
        (field (name "MANUFACTURER") "Bourns")
        (field (name "MANUFACTURER PART NUMBER") "CRL1206-FV-R024ELF")
      )
      (libsource (lib "Sykam-LagerBauteile1-B") (part "R_24mR_CRL1206-FV-R024ELF"))
    )
    (comp (ref "R47")
      (value "15mR")
      (footprint "R1206")
      (description "Res Metal Strip 1206 0.015 Ohm 1% 1/4W 75ppm/C Molded SMD SMD Embossed Plastic T/R")
      (fields
        (field (name "MANUFACTURER") "Vishay Dale")
        (field (name "MANUFACTURER PART NUMBER") "WSL1206R0150FEA")
      )
      (libsource (lib "Sykam-LagerBauteile1-B") (part "R_15mR_WSL1206R0150FEA"))
    )
    (comp (ref "R48")
      (value "27k")
      (footprint "R0805")
      (description "Surface Mount Thick Film Resistor, RC Series, 27 kohm, 125 mW, - 1%, 150 V, 0805 [2012 Metric]")
      (fields
        (field (name "MANUFACTURER") "Yageo")
        (field (name "MANUFACTURER PART NUMBER") "RC0805FR-0727KL")
      )
      (libsource (lib "ToradexMainBoard-V0I1") (part "R_27k_RC0805FR-0727KL"))
    )
    (comp (ref "R49")
      (value "6.2k")
      (footprint "R0805")
      (description "Res Thick Film 0805 6.2K Ohm 1% 0.125W(1/8W) ±100ppm/C Epoxy Pad SMD T/R")
      (fields
        (field (name "MANUFACTURER") "Yageo Phycomp")
        (field (name "MANUFACTURER PART NUMBER") "RC0805FR-076K2L")
      )
      (libsource (lib "ToradexMainBoard-V0I1") (part "R_6.2k_RC0805FR-076K2L"))
    )
    (comp (ref "T1")
      (value "FDS6982AS")
      (footprint "SOIC127P600X173-8N")
      (description "FAIRCHILD SEMICONDUCTOR   FDS6982AS   MOSFET, NN-CH, 30V, 8.6A, 8-SOIC, RL")
      (fields
        (field (name "MANUFACTURER PART NO.") "FDS6982AS")
        (field (name "MANUFACTURER") "ON Semiconductor / Fairchild")
        (field (name "PCBCHECKED") "initials after Checked")
        (field (name "SCHCHECKED") "initials after Checked")
      )
      (libsource (lib "Evaluation Board") (part "T-Fairchild-FDS6982AS-N"))
    )
    (comp (ref "T2")
      (value "FDS6982AS")
      (footprint "SOIC127P600X173-8N")
      (description "FAIRCHILD SEMICONDUCTOR   FDS6982AS   MOSFET, NN-CH, 30V, 8.6A, 8-SOIC, RL")
      (fields
        (field (name "MANUFACTURER PART NO.") "FDS6982AS")
        (field (name "MANUFACTURER") "ON Semiconductor / Fairchild")
        (field (name "PCBCHECKED") "initials after Checked")
        (field (name "SCHCHECKED") "initials after Checked")
      )
      (libsource (lib "Evaluation Board") (part "T-Fairchild-FDS6982AS-N"))
    )
    (comp (ref "X2")
      (value "PT 1,5/ 2-5,0-H - 1935161")
      (footprint "CON_1935161-THT")
      (description "Conn Terminal Blocks 2 POS 5mm Solder ST Thru-Hole 16A")
      (fields
        (field (name "MANUFACTURER") "Phoenix Contact")
        (field (name "MANUFACTURER PART NUMBER") "1935161")
      )
      (libsource (lib "ToradexMainBoard-V0I1") (part "CON_1935161"))
    )
    (comp (ref "X3")
      (value "B2B-XH-A(LF)(SN)")
      (footprint "CON_2p_JST-B2B-XH-A_V")
      (description "Conn Shrouded Header (4 Sides) HDR 2 POS 2.5mm Solder ST Thru-Hole Box")
      (fields (field (name "MANUFACTURER") "JST"))
      (libsource (lib "Sykam-LagerBauteile1-B") (part "CON_2p_B2B-XH-A(LF)(SN)"))
    )
  )
  (nets
    (net (code "1") (name "+3.3V") (class "Default")
      (node (ref "C54") (pin "2") (pinfunction "2_2") (pintype "passive"))
      (node (ref "C56") (pin "1") (pinfunction "1_1") (pintype "passive"))
      (node (ref "C59") (pin "1") (pinfunction "1_1") (pintype "passive"))
      (node (ref "C60") (pin "1") (pinfunction "1_1") (pintype "passive"))
      (node (ref "C62") (pin "1") (pinfunction "1_1") (pintype "passive"))
      (node (ref "IC4") (pin "8") (pinfunction "VO_8") (pintype "input"))
      (node (ref "L5") (pin "2") (pinfunction "2_2") (pintype "passive"))
    )
    (net (code "2") (name "+5V") (class "Default")
      (node (ref "C40") (pin "2") (pinfunction "2_2") (pintype "passive"))
      (node (ref "C53") (pin "2") (pinfunction "2_2") (pintype "passive"))
      (node (ref "C55") (pin "1") (pinfunction "1_1") (pintype "passive"))
      (node (ref "C57") (pin "1") (pinfunction "1_1") (pintype "passive"))
      (node (ref "C58") (pin "1") (pinfunction "1_1") (pintype "passive"))
      (node (ref "C61") (pin "1") (pinfunction "1_1") (pintype "passive"))
      (node (ref "IC4") (pin "1") (pinfunction "VO_1") (pintype "input"))
      (node (ref "IC5") (pin "5") (pinfunction "Vcc_5") (pintype "passive"))
      (node (ref "L6") (pin "2") (pinfunction "2_2") (pintype "passive"))
    )
    (net (code "3") (name "+12V") (class "Default")
      (node (ref "L4") (pin "2") (pinfunction "2_2") (pintype "passive"))
    )
    (net (code "4") (name "+24V") (class "Default")
      (node (ref "C30") (pin "2") (pinfunction "2_2") (pintype "passive"))
      (node (ref "C33") (pin "1") (pinfunction "1_1") (pintype "passive"))
      (node (ref "C34") (pin "1") (pinfunction "1_1") (pintype "passive"))
      (node (ref "C35") (pin "1") (pinfunction "1_1") (pintype "passive"))
      (node (ref "C36") (pin "2") (pinfunction "2_2") (pintype "passive"))
      (node (ref "C39") (pin "2") (pinfunction "2_2") (pintype "passive"))
      (node (ref "C47") (pin "2") (pinfunction "2_2") (pintype "passive"))
      (node (ref "C48") (pin "2") (pinfunction "2_2") (pintype "passive"))
      (node (ref "C49") (pin "2") (pinfunction "2_2") (pintype "passive"))
      (node (ref "C50") (pin "2") (pinfunction "2_2") (pintype "passive"))
      (node (ref "D6") (pin "1") (pinfunction "C_1") (pintype "passive"))
      (node (ref "IC2") (pin "9") (pinfunction "SENSE-_9") (pintype "input"))
      (node (ref "IC4") (pin "22") (pinfunction "VIN_22") (pintype "power_in"))
      (node (ref "L1") (pin "1") (pinfunction "1_1") (pintype "passive"))
      (node (ref "R23") (pin "2") (pinfunction "2_2") (pintype "passive"))
      (node (ref "R24") (pin "2") (pinfunction "2_2") (pintype "passive"))
      (node (ref "R48") (pin "2") (pinfunction "2_2") (pintype "passive"))
      (node (ref "T1") (pin "5") (pinfunction "D_5") (pintype "passive"))
      (node (ref "T1") (pin "6") (pinfunction "D_6") (pintype "passive"))
      (node (ref "T2") (pin "5") (pinfunction "D_5") (pintype "passive"))
      (node (ref "T2") (pin "6") (pinfunction "D_6") (pintype "passive"))
      (node (ref "X3") (pin "1") (pintype "passive"))
    )
    (net (code "5") (name "+48V") (class "Default")
      (node (ref "C15") (pin "1") (pinfunction "1_1") (pintype "passive"))
      (node (ref "C16") (pin "1") (pinfunction "1_1") (pintype "passive"))
      (node (ref "C19") (pin "1") (pinfunction "1_1") (pintype "passive"))
      (node (ref "C23") (pin "1") (pinfunction "1_1") (pintype "passive"))
      (node (ref "C29") (pin "1") (pinfunction "1_1") (pintype "passive"))
      (node (ref "D2") (pin "1") (pinfunction "K_1") (pintype "passive"))
      (node (ref "F5") (pin "2") (pinfunction "2_2") (pintype "passive"))
      (node (ref "IC2") (pin "1") (pinfunction "VIN_1") (pintype "power_in"))
      (node (ref "Q1") (pin "5") (pinfunction "D_5") (pintype "passive"))
      (node (ref "Q1") (pin "6") (pinfunction "D_6") (pintype "passive"))
      (node (ref "Q1") (pin "7") (pinfunction "D_7") (pintype "passive"))
      (node (ref "Q1") (pin "8") (pinfunction "D_8") (pintype "passive"))
      (node (ref "Q1") (pin "9") (pinfunction "D_9") (pintype "passive"))
      (node (ref "R13") (pin "1") (pinfunction "1_1") (pintype "passive"))
    )
    (net (code "6") (name "/DO_PCB-Fan-ON-OFF(141)") (class "Default")
      (node (ref "R32") (pin "1") (pinfunction "1_1") (pintype "passive"))
    )
    (net (code "7") (name "/PWR-ON-3.3V_5V") (class "Default")
      (node (ref "C51") (pin "2") (pinfunction "2_2") (pintype "passive"))
      (node (ref "C52") (pin "2") (pinfunction "2_2") (pintype "passive"))
      (node (ref "D7") (pin "3") (pinfunction "K_3") (pintype "passive"))
      (node (ref "R26") (pin "2") (pinfunction "2_2") (pintype "passive"))
      (node (ref "R29") (pin "1") (pinfunction "1_1") (pintype "passive"))
      (node (ref "R30") (pin "1") (pinfunction "1_1") (pintype "passive"))
      (node (ref "R48") (pin "1") (pinfunction "1_1") (pintype "passive"))
      (node (ref "R49") (pin "2") (pinfunction "2_2") (pintype "passive"))
    )
    (net (code "8") (name "Chassis_GND") (class "Default")
      (node (ref "C29") (pin "2") (pinfunction "2_2") (pintype "passive"))
      (node (ref "C34") (pin "2") (pinfunction "2_2") (pintype "passive"))
      (node (ref "C57") (pin "2") (pinfunction "2_2") (pintype "passive"))
      (node (ref "C59") (pin "2") (pinfunction "2_2") (pintype "passive"))
    )
    (net (code "9") (name "GND") (class "Default")
      (node (ref "C15") (pin "2") (pinfunction "2_2") (pintype "passive"))
      (node (ref "C16") (pin "2") (pinfunction "2_2") (pintype "passive"))
      (node (ref "C17") (pin "1") (pinfunction "1_1") (pintype "passive"))
      (node (ref "C18") (pin "2") (pinfunction "2_2") (pintype "passive"))
      (node (ref "C19") (pin "2") (pinfunction "2_2") (pintype "passive"))
      (node (ref "C20") (pin "2") (pinfunction "2_2") (pintype "passive"))
      (node (ref "C21") (pin "1") (pinfunction "1_1") (pintype "passive"))
      (node (ref "C22") (pin "1") (pinfunction "1_1") (pintype "passive"))
      (node (ref "C23") (pin "2") (pinfunction "2_2") (pintype "passive"))
      (node (ref "C24") (pin "1") (pinfunction "1_1") (pintype "passive"))
      (node (ref "C25") (pin "1") (pinfunction "1_1") (pintype "passive"))
      (node (ref "C27") (pin "1") (pinfunction "1_1") (pintype "passive"))
      (node (ref "C31") (pin "2") (pinfunction "2_2") (pintype "passive"))
      (node (ref "C32") (pin "2") (pinfunction "2_2") (pintype "passive"))
      (node (ref "C33") (pin "2") (pinfunction "2_2") (pintype "passive"))
      (node (ref "C35") (pin "2") (pinfunction "2_2") (pintype "passive"))
      (node (ref "C36") (pin "1") (pinfunction "1_1") (pintype "passive"))
      (node (ref "C37") (pin "1") (pinfunction "1_1") (pintype "passive"))
      (node (ref "C38") (pin "1") (pinfunction "1_1") (pintype "passive"))
      (node (ref "C39") (pin "1") (pinfunction "1_1") (pintype "passive"))
      (node (ref "C40") (pin "1") (pinfunction "1_1") (pintype "passive"))
      (node (ref "C42") (pin "2") (pinfunction "2_2") (pintype "passive"))
      (node (ref "C43") (pin "2") (pinfunction "2_2") (pintype "passive"))
      (node (ref "C45") (pin "2") (pinfunction "2_2") (pintype "passive"))
      (node (ref "C46") (pin "1") (pinfunction "1_1") (pintype "passive"))
      (node (ref "C47") (pin "1") (pinfunction "1_1") (pintype "passive"))
      (node (ref "C48") (pin "1") (pinfunction "1_1") (pintype "passive"))
      (node (ref "C49") (pin "1") (pinfunction "1_1") (pintype "passive"))
      (node (ref "C50") (pin "1") (pinfunction "1_1") (pintype "passive"))
      (node (ref "C51") (pin "1") (pinfunction "1_1") (pintype "passive"))
      (node (ref "C52") (pin "1") (pinfunction "1_1") (pintype "passive"))
      (node (ref "C53") (pin "1") (pinfunction "1_1") (pintype "passive"))
      (node (ref "C54") (pin "1") (pinfunction "1_1") (pintype "passive"))
      (node (ref "C55") (pin "2") (pinfunction "2_2") (pintype "passive"))
      (node (ref "C56") (pin "2") (pinfunction "2_2") (pintype "passive"))
      (node (ref "C58") (pin "2") (pinfunction "2_2") (pintype "passive"))
      (node (ref "C60") (pin "2") (pinfunction "2_2") (pintype "passive"))
      (node (ref "C61") (pin "2") (pinfunction "2_2") (pintype "passive"))
      (node (ref "C62") (pin "2") (pinfunction "2_2") (pintype "passive"))
      (node (ref "D2") (pin "2") (pinfunction "A_2") (pintype "passive"))
      (node (ref "D4") (pin "2") (pinfunction "A_2") (pintype "passive"))
      (node (ref "D5") (pin "2") (pinfunction "A_2") (pintype "passive"))
      (node (ref "D7") (pin "1") (pinfunction "A_1") (pintype "passive"))
      (node (ref "IC2") (pin "11") (pinfunction "PGND_11") (pintype "power_in"))
      (node (ref "IC2") (pin "17") (pinfunction "EP_17") (pintype "power_in"))
      (node (ref "IC2") (pin "5") (pinfunction "BURST_EN_5") (pintype "input"))
      (node (ref "IC2") (pin "8") (pinfunction "SGND_8") (pintype "power_in"))
      (node (ref "IC3") (pin "4") (pinfunction "GND_4") (pintype "power_in"))
      (node (ref "IC3") (pin "6") (pinfunction "SYNC_6") (pintype "input"))
      (node (ref "IC4") (pin "17") (pinfunction "PGND_17") (pintype "power_in"))
      (node (ref "IC4") (pin "24") (pinfunction "PGND_24") (pintype "power_in"))
      (node (ref "IC4") (pin "32") (pinfunction "GND_32") (pintype "power_in"))
      (node (ref "IC4") (pin "33") (pinfunction "HS_33") (pintype "passive"))
      (node (ref "IC4") (pin "5") (pinfunction "GND_5") (pintype "power_in"))
      (node (ref "IC5") (pin "2") (pinfunction "GND_2") (pintype "passive"))
      (node (ref "Q2") (pin "1") (pinfunction "S_1") (pintype "passive"))
      (node (ref "Q2") (pin "2") (pinfunction "S_2") (pintype "passive"))
      (node (ref "Q2") (pin "3") (pinfunction "S_3") (pintype "passive"))
      (node (ref "R14") (pin "1") (pinfunction "1_1") (pintype "passive"))
      (node (ref "R18") (pin "1") (pinfunction "1_1") (pintype "passive"))
      (node (ref "R20") (pin "1") (pinfunction "1_1") (pintype "passive"))
      (node (ref "R22") (pin "1") (pinfunction "1_1") (pintype "passive"))
      (node (ref "R25") (pin "1") (pinfunction "1_1") (pintype "passive"))
      (node (ref "R27") (pin "1") (pinfunction "1_1") (pintype "passive"))
      (node (ref "R31") (pin "1") (pinfunction "1_1") (pintype "passive"))
      (node (ref "R37") (pin "1") (pinfunction "1_1") (pintype "passive"))
      (node (ref "R38") (pin "1") (pinfunction "1_1") (pintype "passive"))
      (node (ref "R43") (pin "1") (pinfunction "1_1") (pintype "passive"))
      (node (ref "R46") (pin "2") (pinfunction "2_2") (pintype "passive"))
      (node (ref "R47") (pin "2") (pinfunction "2_2") (pintype "passive"))
      (node (ref "R49") (pin "1") (pinfunction "1_1") (pintype "passive"))
      (node (ref "X2") (pin "2") (pinfunction "GND_IN_2") (pintype "passive"))
    )
    (net (code "10") (name "Net-(C17-Pad2)") (class "Default")
      (node (ref "C17") (pin "2") (pinfunction "2_2") (pintype "passive"))
      (node (ref "R12") (pin "1") (pinfunction "1_1") (pintype "passive"))
    )
    (net (code "11") (name "Net-(C26-Pad2)") (class "Default")
      (node (ref "C26") (pin "2") (pinfunction "2_2") (pintype "passive"))
      (node (ref "C27") (pin "2") (pinfunction "2_2") (pintype "passive"))
      (node (ref "R18") (pin "2") (pinfunction "2_2") (pintype "passive"))
    )
    (net (code "12") (name "Net-(C30-Pad1)") (class "Default")
      (node (ref "C30") (pin "1") (pinfunction "1_1") (pintype "passive"))
      (node (ref "R19") (pin "2") (pinfunction "2_2") (pintype "passive"))
    )
    (net (code "13") (name "Net-(C37-Pad2)") (class "Default")
      (node (ref "C37") (pin "2") (pinfunction "2_2") (pintype "passive"))
      (node (ref "R33") (pin "1") (pinfunction "1_1") (pintype "passive"))
    )
    (net (code "14") (name "Net-(C38-Pad2)") (class "Default")
      (node (ref "C38") (pin "2") (pinfunction "2_2") (pintype "passive"))
      (node (ref "R34") (pin "1") (pinfunction "1_1") (pintype "passive"))
    )
    (net (code "15") (name "Net-(D3-A)") (class "Default")
      (node (ref "C25") (pin "2") (pinfunction "2_2") (pintype "passive"))
      (node (ref "D3") (pin "1") (pinfunction "A_1") (pintype "passive"))
      (node (ref "IC2") (pin "12") (pinfunction "VCC_12") (pintype "power_in"))
    )
    (net (code "16") (name "Net-(D3-K)") (class "Default")
      (node (ref "C28") (pin "1") (pinfunction "1_1") (pintype "passive"))
      (node (ref "D3") (pin "2") (pinfunction "K_2") (pintype "passive"))
      (node (ref "IC2") (pin "16") (pinfunction "BOOST_16") (pintype "passive"))
    )
    (net (code "17") (name "Net-(D4-C)") (class "Default")
      (node (ref "D4") (pin "1") (pinfunction "C_1") (pintype "passive"))
      (node (ref "IC3") (pin "3") (pinfunction "VSW_3") (pintype "power_in"))
      (node (ref "L2") (pin "1") (pinfunction "1_1") (pintype "passive"))
    )
    (net (code "18") (name "Net-(D5-C)") (class "Default")
      (node (ref "C28") (pin "2") (pinfunction "2_2") (pintype "passive"))
      (node (ref "D5") (pin "1") (pinfunction "C_1") (pintype "passive"))
      (node (ref "L3") (pin "1") (pinfunction "1_1") (pintype "passive"))
      (node (ref "Q1") (pin "1") (pinfunction "S_1") (pintype "passive"))
      (node (ref "Q1") (pin "2") (pinfunction "S_2") (pintype "passive"))
      (node (ref "Q1") (pin "3") (pinfunction "S_3") (pintype "passive"))
      (node (ref "R16") (pin "2") (pinfunction "2_2") (pintype "passive"))
      (node (ref "R17") (pin "2") (pinfunction "2_2") (pintype "passive"))
    )
    (net (code "19") (name "Net-(D6-A)") (class "Default")
      (node (ref "D6") (pin "2") (pinfunction "A_2") (pintype "passive"))
      (node (ref "Q2") (pin "5") (pinfunction "D_5") (pintype "passive"))
      (node (ref "Q2") (pin "6") (pinfunction "D_6") (pintype "passive"))
      (node (ref "Q2") (pin "7") (pinfunction "D_7") (pintype "passive"))
      (node (ref "Q2") (pin "8") (pinfunction "D_8") (pintype "passive"))
      (node (ref "X3") (pin "2") (pintype "passive"))
    )
    (net (code "20") (name "Net-(IC2-CSS)") (class "Default")
      (node (ref "IC2") (pin "4") (pinfunction "CSS_4") (pintype "input"))
      (node (ref "R19") (pin "1") (pinfunction "1_1") (pintype "passive"))
    )
    (net (code "21") (name "Net-(IC2-SENSE+)") (class "Default")
      (node (ref "IC2") (pin "10") (pinfunction "SENSE+_10") (pintype "input"))
      (node (ref "L3") (pin "2") (pinfunction "2_2") (pintype "passive"))
      (node (ref "R23") (pin "1") (pinfunction "1_1") (pintype "passive"))
    )
    (net (code "22") (name "Net-(IC2-SW)") (class "Default")
      (node (ref "IC2") (pin "14") (pinfunction "SW_14") (pintype "passive"))
      (node (ref "R16") (pin "1") (pinfunction "1_1") (pintype "passive"))
    )
    (net (code "23") (name "Net-(IC2-TG)") (class "Default")
      (node (ref "IC2") (pin "15") (pinfunction "TG_15") (pintype "output"))
      (node (ref "R15") (pin "1") (pinfunction "1_1") (pintype "passive"))
    )
    (net (code "24") (name "Net-(IC2-VC)") (class "Default")
      (node (ref "C21") (pin "2") (pinfunction "2_2") (pintype "passive"))
      (node (ref "IC2") (pin "7") (pinfunction "VC_7") (pintype "passive"))
      (node (ref "R12") (pin "2") (pinfunction "2_2") (pintype "passive"))
    )
    (net (code "25") (name "Net-(IC2-VFB)") (class "Default")
      (node (ref "IC2") (pin "6") (pinfunction "VFB_6") (pintype "input"))
      (node (ref "R24") (pin "1") (pinfunction "1_1") (pintype "passive"))
      (node (ref "R25") (pin "2") (pinfunction "2_2") (pintype "passive"))
    )
    (net (code "26") (name "Net-(IC2-~{SHDN})") (class "Default")
      (node (ref "IC2") (pin "3") (pinfunction "~{SHDN}_3") (pintype "input"))
      (node (ref "R13") (pin "2") (pinfunction "2_2") (pintype "passive"))
      (node (ref "R14") (pin "2") (pinfunction "2_2") (pintype "passive"))
    )
    (net (code "27") (name "Net-(IC3-FB)") (class "Default")
      (node (ref "IC3") (pin "7") (pinfunction "FB_7") (pintype "input"))
      (node (ref "R20") (pin "2") (pinfunction "2_2") (pintype "passive"))
      (node (ref "R21") (pin "1") (pinfunction "1_1") (pintype "passive"))
      (node (ref "R22") (pin "2") (pinfunction "2_2") (pintype "passive"))
    )
    (net (code "28") (name "Net-(IC3-VC)") (class "Default")
      (node (ref "C26") (pin "1") (pinfunction "1_1") (pintype "passive"))
      (node (ref "IC3") (pin "8") (pinfunction "VC_8") (pintype "passive"))
    )
    (net (code "29") (name "Net-(IC3-VCC)") (class "Default")
      (node (ref "C24") (pin "2") (pinfunction "2_2") (pintype "passive"))
      (node (ref "C31") (pin "1") (pinfunction "1_1") (pintype "passive"))
      (node (ref "C32") (pin "1") (pinfunction "1_1") (pintype "passive"))
      (node (ref "IC3") (pin "2") (pinfunction "VCC_2") (pintype "power_in"))
      (node (ref "L2") (pin "2") (pinfunction "2_2") (pintype "passive"))
      (node (ref "L4") (pin "1") (pinfunction "1_1") (pintype "passive"))
      (node (ref "R21") (pin "2") (pinfunction "2_2") (pintype "passive"))
    )
    (net (code "30") (name "Net-(IC3-VIN)") (class "Default")
      (node (ref "C18") (pin "1") (pinfunction "1_1") (pintype "passive"))
      (node (ref "C20") (pin "1") (pinfunction "1_1") (pintype "passive"))
      (node (ref "IC3") (pin "5") (pinfunction "VIN_5") (pintype "power_in"))
      (node (ref "L1") (pin "2") (pinfunction "2_2") (pintype "passive"))
    )
    (net (code "31") (name "Net-(IC3-~{SHDN})") (class "Default")
      (node (ref "C22") (pin "2") (pinfunction "2_2") (pintype "passive"))
      (node (ref "IC3") (pin "1") (pinfunction "~{SHDN}_1") (pintype "input"))
    )
    (net (code "32") (name "Net-(IC4A-EN5)") (class "Default")
      (node (ref "IC4") (pin "9") (pinfunction "EN5_9") (pintype "input"))
      (node (ref "R30") (pin "2") (pinfunction "2_2") (pintype "passive"))
    )
    (net (code "33") (name "Net-(IC4A-TONSEL)") (class "Default")
      (node (ref "IC4") (pin "31") (pinfunction "TONSEL_31") (pintype "input"))
      (node (ref "R31") (pin "2") (pinfunction "2_2") (pintype "passive"))
    )
    (net (code "34") (name "Net-(IC4B-COMP)") (class "Default")
      (node (ref "IC4") (pin "2") (pinfunction "COMP_2") (pintype "output"))
      (node (ref "R34") (pin "2") (pinfunction "2_2") (pintype "passive"))
    )
    (net (code "35") (name "Net-(IC4B-CS)") (class "Default")
      (node (ref "IC4") (pin "23") (pinfunction "CS_23") (pintype "input"))
      (node (ref "R44") (pin "1") (pinfunction "1_1") (pintype "passive"))
      (node (ref "R47") (pin "1") (pinfunction "1_1") (pintype "passive"))
      (node (ref "T1") (pin "1") (pinfunction "S_1") (pintype "passive"))
    )
    (net (code "36") (name "Net-(IC4B-DRVH)") (class "Default")
      (node (ref "IC4") (pin "27") (pinfunction "DRVH_27") (pintype "output"))
      (node (ref "R41") (pin "1") (pinfunction "1_1") (pintype "passive"))
    )
    (net (code "37") (name "Net-(IC4B-DRVL)") (class "Default")
      (node (ref "IC4") (pin "25") (pinfunction "DRVL_25") (pintype "output"))
      (node (ref "T1") (pin "2") (pinfunction "G_2") (pintype "passive"))
    )
    (net (code "38") (name "Net-(IC4B-EN)") (class "Default")
      (node (ref "IC4") (pin "29") (pinfunction "EN_29") (pintype "input"))
      (node (ref "R26") (pin "1") (pinfunction "1_1") (pintype "passive"))
      (node (ref "R27") (pin "2") (pinfunction "2_2") (pintype "passive"))
    )
    (net (code "39") (name "Net-(IC4B-LL)") (class "Default")
      (node (ref "C41") (pin "2") (pinfunction "2_2") (pintype "passive"))
      (node (ref "IC4") (pin "26") (pinfunction "LL_26") (pintype "bidirectional"))
      (node (ref "L6") (pin "1") (pinfunction "1_1") (pintype "passive"))
      (node (ref "T1") (pin "3") (pinfunction "S_3") (pintype "passive"))
      (node (ref "T1") (pin "7") (pinfunction "D_7") (pintype "passive"))
      (node (ref "T1") (pin "8") (pinfunction "D_8") (pintype "passive"))
    )
    (net (code "40") (name "Net-(IC4B-PGOOD)") (class "Default")
      (node (ref "IC4") (pin "30") (pinfunction "PGOOD_30") (pintype "output"))
      (node (ref "R28") (pin "1") (pinfunction "1_1") (pintype "passive"))
      (node (ref "R35") (pin "1") (pinfunction "1_1") (pintype "passive"))
    )
    (net (code "41") (name "Net-(IC4B-VBST)") (class "Default")
      (node (ref "C41") (pin "1") (pinfunction "1_1") (pintype "passive"))
      (node (ref "IC4") (pin "28") (pinfunction "VBST_28") (pintype "power_in"))
    )
    (net (code "42") (name "Net-(IC4C-COMP)") (class "Default")
      (node (ref "IC4") (pin "7") (pinfunction "COMP_7") (pintype "output"))
      (node (ref "R33") (pin "2") (pinfunction "2_2") (pintype "passive"))
    )
    (net (code "43") (name "Net-(IC4C-CS)") (class "Default")
      (node (ref "IC4") (pin "18") (pinfunction "CS_18") (pintype "input"))
      (node (ref "R45") (pin "1") (pinfunction "1_1") (pintype "passive"))
      (node (ref "R46") (pin "1") (pinfunction "1_1") (pintype "passive"))
      (node (ref "T2") (pin "1") (pinfunction "S_1") (pintype "passive"))
    )
    (net (code "44") (name "Net-(IC4C-DRVH)") (class "Default")
      (node (ref "IC4") (pin "14") (pinfunction "DRVH_14") (pintype "output"))
      (node (ref "R40") (pin "1") (pinfunction "1_1") (pintype "passive"))
    )
    (net (code "45") (name "Net-(IC4C-DRVL)") (class "Default")
      (node (ref "IC4") (pin "16") (pinfunction "DRVL_16") (pintype "output"))
      (node (ref "T2") (pin "2") (pinfunction "G_2") (pintype "passive"))
    )
    (net (code "46") (name "Net-(IC4C-EN)") (class "Default")
      (node (ref "IC4") (pin "12") (pinfunction "EN_12") (pintype "input"))
      (node (ref "R28") (pin "2") (pinfunction "2_2") (pintype "passive"))
      (node (ref "R29") (pin "2") (pinfunction "2_2") (pintype "passive"))
    )
    (net (code "47") (name "Net-(IC4C-LL)") (class "Default")
      (node (ref "C44") (pin "2") (pinfunction "2_2") (pintype "passive"))
      (node (ref "IC4") (pin "15") (pinfunction "LL_15") (pintype "bidirectional"))
      (node (ref "L5") (pin "1") (pinfunction "1_1") (pintype "passive"))
      (node (ref "T2") (pin "3") (pinfunction "S_3") (pintype "passive"))
      (node (ref "T2") (pin "7") (pinfunction "D_7") (pintype "passive"))
      (node (ref "T2") (pin "8") (pinfunction "D_8") (pintype "passive"))
    )
    (net (code "48") (name "Net-(IC4C-PGOOD)") (class "Default")
      (node (ref "IC4") (pin "11") (pinfunction "PGOOD_11") (pintype "output"))
      (node (ref "R36") (pin "1") (pinfunction "1_1") (pintype "passive"))
    )
    (net (code "49") (name "Net-(IC4C-VBST)") (class "Default")
      (node (ref "C44") (pin "1") (pinfunction "1_1") (pintype "passive"))
      (node (ref "IC4") (pin "13") (pinfunction "VBST_13") (pintype "passive"))
    )
    (net (code "50") (name "Net-(IC5-I0)") (class "Default")
      (node (ref "IC5") (pin "3") (pinfunction "I0_3") (pintype "input"))
      (node (ref "R32") (pin "2") (pinfunction "2_2") (pintype "passive"))
      (node (ref "R37") (pin "2") (pinfunction "2_2") (pintype "passive"))
    )
    (net (code "51") (name "Net-(IC5-I1)") (class "Default")
      (node (ref "IC5") (pin "1") (pinfunction "I1_1") (pintype "input"))
      (node (ref "IC5") (pin "6") (pinfunction "I2_6") (pintype "input"))
      (node (ref "R38") (pin "2") (pinfunction "2_2") (pintype "passive"))
    )
    (net (code "52") (name "Net-(IC5-Y)") (class "Default")
      (node (ref "IC5") (pin "4") (pinfunction "Y_4") (pintype "output"))
      (node (ref "R39") (pin "1") (pinfunction "1_1") (pintype "passive"))
    )
    (net (code "53") (name "Net-(Q1-G)") (class "Default")
      (node (ref "Q1") (pin "4") (pinfunction "G_4") (pintype "passive"))
      (node (ref "R15") (pin "2") (pinfunction "2_2") (pintype "passive"))
      (node (ref "R17") (pin "1") (pinfunction "1_1") (pintype "passive"))
    )
    (net (code "54") (name "Net-(Q2-G)") (class "Default")
      (node (ref "Q2") (pin "4") (pinfunction "G_4") (pintype "passive"))
      (node (ref "R39") (pin "2") (pinfunction "2_2") (pintype "passive"))
      (node (ref "R43") (pin "2") (pinfunction "2_2") (pintype "passive"))
    )
    (net (code "55") (name "Net-(T1B-G)") (class "Default")
      (node (ref "R41") (pin "2") (pinfunction "2_2") (pintype "passive"))
      (node (ref "T1") (pin "4") (pinfunction "G_4") (pintype "passive"))
    )
    (net (code "56") (name "Net-(T2B-G)") (class "Default")
      (node (ref "R40") (pin "2") (pinfunction "2_2") (pintype "passive"))
      (node (ref "T2") (pin "4") (pinfunction "G_4") (pintype "passive"))
    )
    (net (code "57") (name "Net-(X2-PWR_IN)") (class "Default")
      (node (ref "F5") (pin "1") (pinfunction "1_1") (pintype "passive"))
      (node (ref "X2") (pin "1") (pinfunction "PWR_IN_1") (pintype "passive"))
    )
    (net (code "58") (name "V5FILT") (class "Default")
      (node (ref "C42") (pin "1") (pinfunction "1_1") (pintype "passive"))
      (node (ref "IC4") (pin "20") (pinfunction "V5FILT_20") (pintype "power_in"))
      (node (ref "IC4") (pin "3") (pinfunction "VFB_3") (pintype "input"))
      (node (ref "IC4") (pin "6") (pinfunction "VFB_6") (pintype "input"))
      (node (ref "R35") (pin "2") (pinfunction "2_2") (pintype "passive"))
      (node (ref "R36") (pin "2") (pinfunction "2_2") (pintype "passive"))
      (node (ref "R42") (pin "1") (pinfunction "1_1") (pintype "passive"))
      (node (ref "R44") (pin "2") (pinfunction "2_2") (pintype "passive"))
      (node (ref "R45") (pin "2") (pinfunction "2_2") (pintype "passive"))
    )
    (net (code "59") (name "VREF2") (class "Default")
      (node (ref "C45") (pin "1") (pinfunction "1_1") (pintype "passive"))
      (node (ref "IC4") (pin "4") (pinfunction "VREF2_4") (pintype "output"))
    )
    (net (code "60") (name "VREG3") (class "Default")
      (node (ref "C43") (pin "1") (pinfunction "1_1") (pintype "passive"))
      (node (ref "IC4") (pin "19") (pinfunction "VREG3_19") (pintype "output"))
    )
    (net (code "61") (name "VREG5") (class "Default")
      (node (ref "C46") (pin "2") (pinfunction "2_2") (pintype "passive"))
      (node (ref "IC4") (pin "10") (pinfunction "EN3_10") (pintype "input"))
      (node (ref "IC4") (pin "21") (pinfunction "VREG5_21") (pintype "output"))
      (node (ref "R42") (pin "2") (pinfunction "2_2") (pintype "passive"))
    )
    (net (code "62") (name "unconnected-(IC2-NC-Pad2)") (class "Default")
      (node (ref "IC2") (pin "2") (pinfunction "NC_2") (pintype "passive+no_connect"))
    )
    (net (code "63") (name "unconnected-(IC2-NC-Pad13)") (class "Default")
      (node (ref "IC2") (pin "13") (pinfunction "NC_13") (pintype "passive+no_connect"))
    )
  )
)
